# led_board_v2.net
KiCad netlist of a schematic drawn in EAGLE
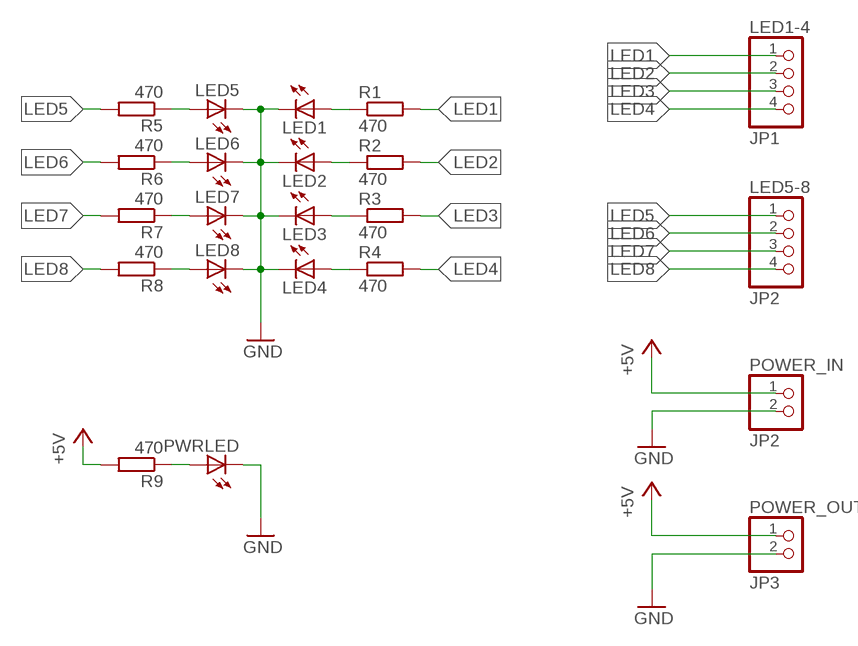
[diagram p0: schematic, sheet 1]

(export (version "E")
  (design (tool "Eeschema 10.0.6"))
  (components
    (comp (ref "LED1")
      (value "LED3MM")
      (footprint "eagle-import:LED3MM")
      (libsource (lib "eagle-import") (part "LED3MM"))
    )
    (comp (ref "LED1-4")
      (value "JP1")
      (footprint "eagle-import:1X04")
      (libsource (lib "eagle-import") (part "PINHD-1X4"))
    )
    (comp (ref "LED2")
      (value "LED3MM")
      (footprint "eagle-import:LED3MM")
      (libsource (lib "eagle-import") (part "LED3MM"))
    )
    (comp (ref "LED3")
      (value "LED3MM")
      (footprint "eagle-import:LED3MM")
      (libsource (lib "eagle-import") (part "LED3MM"))
    )
    (comp (ref "LED4")
      (value "LED3MM")
      (footprint "eagle-import:LED3MM")
      (libsource (lib "eagle-import") (part "LED3MM"))
    )
    (comp (ref "LED5")
      (value "LED3MM")
      (footprint "eagle-import:LED3MM")
      (libsource (lib "eagle-import") (part "LED3MM"))
    )
    (comp (ref "LED5-8")
      (value "JP2")
      (footprint "eagle-import:1X04")
      (libsource (lib "eagle-import") (part "PINHD-1X4"))
    )
    (comp (ref "LED6")
      (value "LED3MM")
      (footprint "eagle-import:LED3MM")
      (libsource (lib "eagle-import") (part "LED3MM"))
    )
    (comp (ref "LED7")
      (value "LED3MM")
      (footprint "eagle-import:LED3MM")
      (libsource (lib "eagle-import") (part "LED3MM"))
    )
    (comp (ref "LED8")
      (value "LED3MM")
      (footprint "eagle-import:LED3MM")
      (libsource (lib "eagle-import") (part "LED3MM"))
    )
    (comp (ref "POWER_IN")
      (value "JP2")
      (footprint "eagle-import:1X02")
      (libsource (lib "eagle-import") (part "PINHD-1X2"))
    )
    (comp (ref "POWER_OUT")
      (value "JP3")
      (footprint "eagle-import:1X02")
      (libsource (lib "eagle-import") (part "PINHD-1X2"))
    )
    (comp (ref "PWRLED")
      (value "LED3MM")
      (footprint "eagle-import:LED3MM")
      (libsource (lib "eagle-import") (part "LED3MM"))
    )
    (comp (ref "R1")
      (value "470")
      (footprint "eagle-import:R0805")
      (libsource (lib "eagle-import") (part "R-EU_R0805"))
    )
    (comp (ref "R2")
      (value "470")
      (footprint "eagle-import:R0805")
      (libsource (lib "eagle-import") (part "R-EU_R0805"))
    )
    (comp (ref "R3")
      (value "470")
      (footprint "eagle-import:R0805")
      (libsource (lib "eagle-import") (part "R-EU_R0805"))
    )
    (comp (ref "R4")
      (value "470")
      (footprint "eagle-import:R0805")
      (libsource (lib "eagle-import") (part "R-EU_R0805"))
    )
    (comp (ref "R5")
      (value "470")
      (footprint "eagle-import:R0805")
      (libsource (lib "eagle-import") (part "R-EU_R0805"))
    )
    (comp (ref "R6")
      (value "470")
      (footprint "eagle-import:R0805")
      (libsource (lib "eagle-import") (part "R-EU_R0805"))
    )
    (comp (ref "R7")
      (value "470")
      (footprint "eagle-import:R0805")
      (libsource (lib "eagle-import") (part "R-EU_R0805"))
    )
    (comp (ref "R8")
      (value "470")
      (footprint "eagle-import:R0805")
      (libsource (lib "eagle-import") (part "R-EU_R0805"))
    )
    (comp (ref "R9")
      (value "470")
      (footprint "eagle-import:R0805")
      (libsource (lib "eagle-import") (part "R-EU_R0805"))
    )
  )
  (nets
    (net (code "1") (name "+5V") (class "Default")
      (node (ref "POWER_IN") (pin "1") (pinfunction "1_1") (pintype "passive"))
      (node (ref "POWER_OUT") (pin "1") (pinfunction "1_1") (pintype "passive"))
      (node (ref "R9") (pin "2") (pinfunction "2_2") (pintype "passive"))
    )
    (net (code "2") (name "GND") (class "Default")
      (node (ref "LED1") (pin "K") (pinfunction "C_K") (pintype "passive"))
      (node (ref "LED2") (pin "K") (pinfunction "C_K") (pintype "passive"))
      (node (ref "LED3") (pin "K") (pinfunction "C_K") (pintype "passive"))
      (node (ref "LED4") (pin "K") (pinfunction "C_K") (pintype "passive"))
      (node (ref "LED5") (pin "K") (pinfunction "C_K") (pintype "passive"))
      (node (ref "LED6") (pin "K") (pinfunction "C_K") (pintype "passive"))
      (node (ref "LED7") (pin "K") (pinfunction "C_K") (pintype "passive"))
      (node (ref "LED8") (pin "K") (pinfunction "C_K") (pintype "passive"))
      (node (ref "POWER_IN") (pin "2") (pinfunction "2_2") (pintype "passive"))
      (node (ref "POWER_OUT") (pin "2") (pinfunction "2_2") (pintype "passive"))
      (node (ref "PWRLED") (pin "K") (pinfunction "C_K") (pintype "passive"))
    )
    (net (code "3") (name "LED1") (class "Default")
      (node (ref "LED1-4") (pin "1") (pinfunction "1_1") (pintype "passive"))
      (node (ref "R1") (pin "2") (pinfunction "2_2") (pintype "passive"))
    )
    (net (code "4") (name "LED2") (class "Default")
      (node (ref "LED1-4") (pin "2") (pinfunction "2_2") (pintype "passive"))
      (node (ref "R2") (pin "2") (pinfunction "2_2") (pintype "passive"))
    )
    (net (code "5") (name "LED3") (class "Default")
      (node (ref "LED1-4") (pin "3") (pinfunction "3_3") (pintype "passive"))
      (node (ref "R3") (pin "2") (pinfunction "2_2") (pintype "passive"))
    )
    (net (code "6") (name "LED4") (class "Default")
      (node (ref "LED1-4") (pin "4") (pinfunction "4_4") (pintype "passive"))
      (node (ref "R4") (pin "2") (pinfunction "2_2") (pintype "passive"))
    )
    (net (code "7") (name "LED5") (class "Default")
      (node (ref "LED5-8") (pin "1") (pinfunction "1_1") (pintype "passive"))
      (node (ref "R5") (pin "2") (pinfunction "2_2") (pintype "passive"))
    )
    (net (code "8") (name "LED6") (class "Default")
      (node (ref "LED5-8") (pin "2") (pinfunction "2_2") (pintype "passive"))
      (node (ref "R6") (pin "2") (pinfunction "2_2") (pintype "passive"))
    )
    (net (code "9") (name "LED7") (class "Default")
      (node (ref "LED5-8") (pin "3") (pinfunction "3_3") (pintype "passive"))
      (node (ref "R7") (pin "2") (pinfunction "2_2") (pintype "passive"))
    )
    (net (code "10") (name "LED8") (class "Default")
      (node (ref "LED5-8") (pin "4") (pinfunction "4_4") (pintype "passive"))
      (node (ref "R8") (pin "2") (pinfunction "2_2") (pintype "passive"))
    )
    (net (code "11") (name "Net-(LED1-PadA)") (class "Default")
      (node (ref "LED1") (pin "A") (pinfunction "A_A") (pintype "passive"))
      (node (ref "R1") (pin "1") (pinfunction "1_1") (pintype "passive"))
    )
    (net (code "12") (name "Net-(LED2-PadA)") (class "Default")
      (node (ref "LED2") (pin "A") (pinfunction "A_A") (pintype "passive"))
      (node (ref "R2") (pin "1") (pinfunction "1_1") (pintype "passive"))
    )
    (net (code "13") (name "Net-(LED3-PadA)") (class "Default")
      (node (ref "LED3") (pin "A") (pinfunction "A_A") (pintype "passive"))
      (node (ref "R3") (pin "1") (pinfunction "1_1") (pintype "passive"))
    )
    (net (code "14") (name "Net-(LED4-PadA)") (class "Default")
      (node (ref "LED4") (pin "A") (pinfunction "A_A") (pintype "passive"))
      (node (ref "R4") (pin "1") (pinfunction "1_1") (pintype "passive"))
    )
    (net (code "15") (name "Net-(LED5-PadA)") (class "Default")
      (node (ref "LED5") (pin "A") (pinfunction "A_A") (pintype "passive"))
      (node (ref "R5") (pin "1") (pinfunction "1_1") (pintype "passive"))
    )
    (net (code "16") (name "Net-(LED6-PadA)") (class "Default")
      (node (ref "LED6") (pin "A") (pinfunction "A_A") (pintype "passive"))
      (node (ref "R6") (pin "1") (pinfunction "1_1") (pintype "passive"))
    )
    (net (code "17") (name "Net-(LED7-PadA)") (class "Default")
      (node (ref "LED7") (pin "A") (pinfunction "A_A") (pintype "passive"))
      (node (ref "R7") (pin "1") (pinfunction "1_1") (pintype "passive"))
    )
    (net (code "18") (name "Net-(LED8-PadA)") (class "Default")
      (node (ref "LED8") (pin "A") (pinfunction "A_A") (pintype "passive"))
      (node (ref "R8") (pin "1") (pinfunction "1_1") (pintype "passive"))
    )
    (net (code "19") (name "Net-(PWRLED-PadA)") (class "Default")
      (node (ref "PWRLED") (pin "A") (pinfunction "A_A") (pintype "passive"))
      (node (ref "R9") (pin "1") (pinfunction "1_1") (pintype "passive"))
    )
  )
)
